# ESP32WROOM.net
KiCad netlist of a schematic drawn in Altium Designer
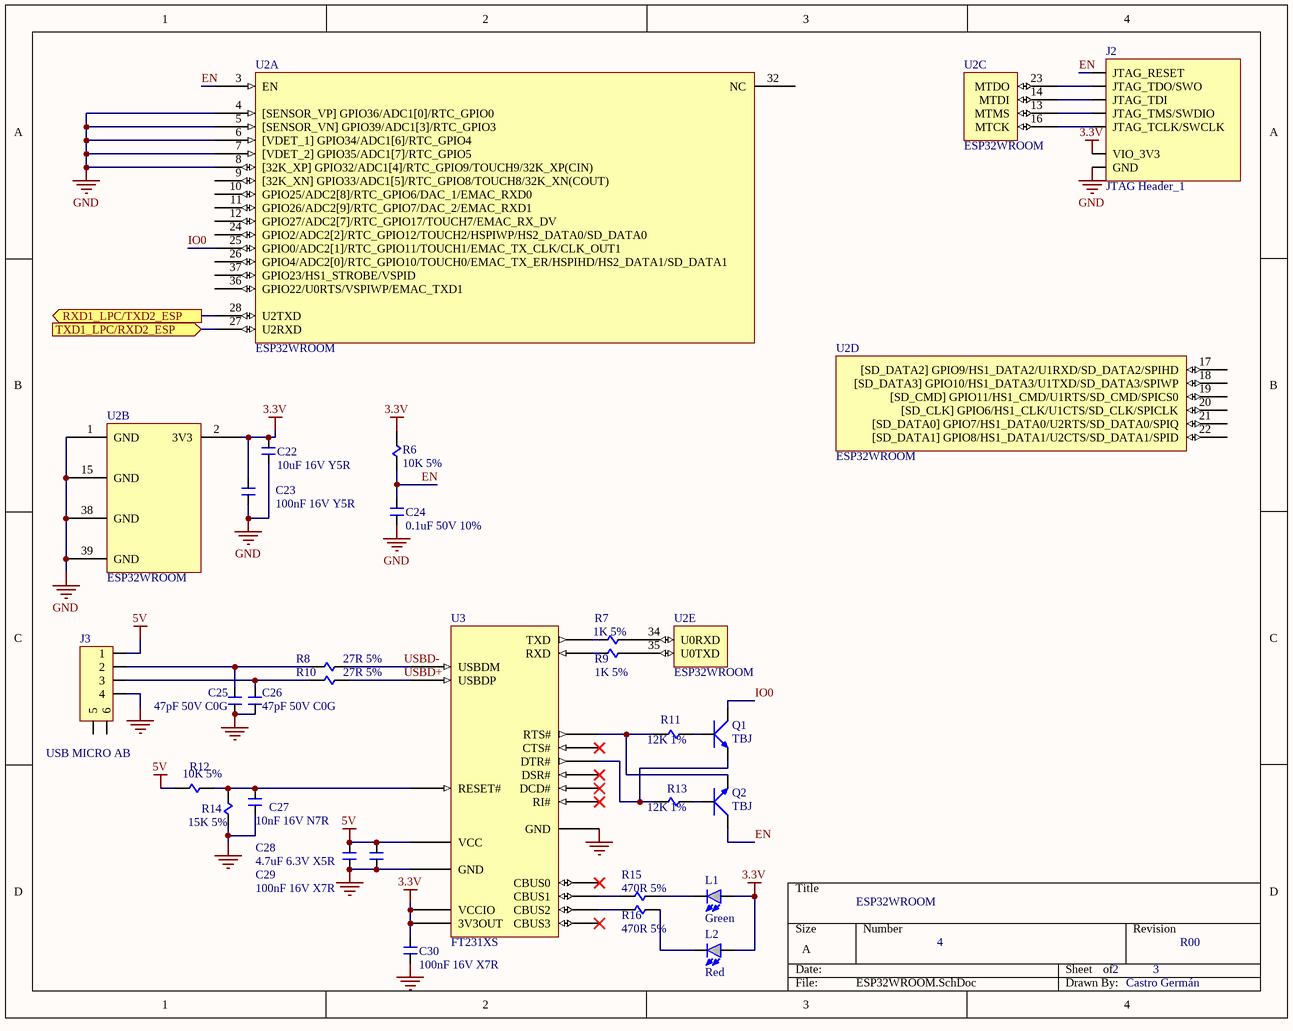
[diagram p0: ESP32WROOM.SchDoc]

(export (version "E")
  (design (tool "Eeschema 10.0.6"))
  (components
    (comp (ref "C22")
      (value "10uF 16V Y5R")
      (footprint "C_0805")
      (description "Capacitor")
      (libsource (lib "MyPro") (part "Capacitor"))
    )
    (comp (ref "C23")
      (value "100nF 16V Y5R")
      (footprint "C_0805")
      (description "Capacitor")
      (libsource (lib "MyPro") (part "Capacitor"))
    )
    (comp (ref "C24")
      (value "0.1uF 50V 10%")
      (footprint "C_0805")
      (description "Capacitor")
      (libsource (lib "MyPro") (part "Capacitor"))
    )
    (comp (ref "C25")
      (value "47pF 50V C0G")
      (footprint "C_0805")
      (description "Capacitor")
      (libsource (lib "BridgeUSB") (part "Capacitor"))
    )
    (comp (ref "C26")
      (value "47pF 50V C0G")
      (footprint "C_0805")
      (description "Capacitor")
      (libsource (lib "BridgeUSB") (part "Capacitor"))
    )
    (comp (ref "C27")
      (value "10nF 16V N7R")
      (footprint "C_0805")
      (description "Capacitor")
      (libsource (lib "BridgeUSB") (part "Capacitor"))
    )
    (comp (ref "C28")
      (value "4.7uF 6.3V X5R")
      (footprint "C_0805")
      (description "Capacitor")
      (libsource (lib "BridgeUSB") (part "Capacitor"))
    )
    (comp (ref "C29")
      (value "100nF 16V X7R")
      (footprint "C_0805")
      (description "Capacitor")
      (libsource (lib "BridgeUSB") (part "Capacitor"))
    )
    (comp (ref "C30")
      (value "100nF 16V X7R")
      (footprint "C_0805")
      (description "Capacitor")
      (libsource (lib "BridgeUSB") (part "Capacitor"))
    )
    (comp (ref "J2")
      (value "JTAG Header_1")
      (footprint "HDRM_2.54mm_1X8")
      (libsource (lib "MyPro") (part "JTAG Header_1"))
    )
    (comp (ref "J3")
      (value "USB MICRO AB")
      (footprint "USB_MICRO_F_AB")
      (libsource (lib "BridgeUSB") (part "Connectorx6"))
    )
    (comp (ref "L1")
      (value "Green")
      (footprint "Led_0805")
      (description "Green LED")
      (libsource (lib "MyPro") (part "Led_G"))
    )
    (comp (ref "L2")
      (value "Red")
      (footprint "Led_0805")
      (description "Red LED")
      (libsource (lib "MyPro") (part "Led_R"))
    )
    (comp (ref "Q1") (value "TBJ") (footprint "SOT-23") (libsource (lib "MyPro") (part "TBJ_NPN")))
    (comp (ref "Q2") (value "TBJ") (footprint "SOT-23") (libsource (lib "MyPro") (part "TBJ_NPN")))
    (comp (ref "R6")
      (value "10K 5%")
      (footprint "R_0805")
      (description "Resistor")
      (libsource (lib "MyPro") (part "Resistor"))
    )
    (comp (ref "R7")
      (value "1K 5%")
      (footprint "R_0805")
      (description "Resistor")
      (libsource (lib "BridgeUSB") (part "Resistor"))
    )
    (comp (ref "R8")
      (value "27R 5%")
      (footprint "R_0805")
      (description "Resistor")
      (libsource (lib "BridgeUSB") (part "Resistor"))
    )
    (comp (ref "R9")
      (value "1K 5%")
      (footprint "R_0805")
      (description "Resistor")
      (libsource (lib "BridgeUSB") (part "Resistor"))
    )
    (comp (ref "R10")
      (value "27R 5%")
      (footprint "R_0805")
      (description "Resistor")
      (libsource (lib "BridgeUSB") (part "Resistor"))
    )
    (comp (ref "R11")
      (value "12K 1%")
      (footprint "R_0805")
      (description "Resistor")
      (libsource (lib "MyPro") (part "Resistor"))
    )
    (comp (ref "R12")
      (value "10K 5%")
      (footprint "R_0805")
      (description "Resistor")
      (libsource (lib "BridgeUSB") (part "Resistor"))
    )
    (comp (ref "R13")
      (value "12K 1%")
      (footprint "R_0805")
      (description "Resistor")
      (libsource (lib "MyPro") (part "Resistor"))
    )
    (comp (ref "R14")
      (value "15K 5%")
      (footprint "R_0805")
      (description "Resistor")
      (libsource (lib "BridgeUSB") (part "Resistor"))
    )
    (comp (ref "R15")
      (value "470R 5%")
      (footprint "R_0805")
      (description "Resistor")
      (libsource (lib "BridgeUSB") (part "Resistor"))
    )
    (comp (ref "R16")
      (value "470R 5%")
      (footprint "R_0805")
      (description "Resistor")
      (libsource (lib "BridgeUSB") (part "Resistor"))
    )
    (comp (ref "U2")
      (value "ESP32WROOM")
      (footprint "ESP32_WROOM - duplicate")
      (libsource (lib "MyPro") (part "ESP32WROOM"))
    )
    (comp (ref "U3") (value "FT231XS") (footprint "SSOP_20") (libsource (lib "MyPro") (part "FT231XS")))
  )
  (nets
    (net (code "1") (name "/EN") (class "Default")
      (node (ref "C24") (pin "1") (pinfunction "A1_1") (pintype "passive"))
      (node (ref "J2") (pin "4") (pinfunction "JTAG_RESET_4") (pintype "passive"))
      (node (ref "Q2") (pin "3") (pinfunction "C_3") (pintype "passive"))
      (node (ref "R6") (pin "1") (pinfunction "P1_1") (pintype "passive"))
      (node (ref "U2") (pin "3") (pinfunction "EN_3") (pintype "input"))
    )
    (net (code "2") (name "/IO0") (class "Default")
      (node (ref "Q1") (pin "3") (pinfunction "C_3") (pintype "passive"))
      (node (ref "U2") (pin "25") (pinfunction "GPIO0/ADC2[1]/RTC_GPIO11/TOUCH1/EMAC_TX_CLK/CLK_OUT1_25") (pintype "bidirectional"))
    )
    (net (code "3") (name "/RXD1_LPC{slash}TXD2_ESP") (class "Default")
      (node (ref "U2") (pin "28") (pinfunction "U2TXD_28") (pintype "bidirectional"))
    )
    (net (code "4") (name "/TXD1_LPC{slash}RXD2_ESP") (class "Default")
      (node (ref "U2") (pin "27") (pinfunction "U2RXD_27") (pintype "bidirectional"))
    )
    (net (code "5") (name "/USBD+") (class "Default")
      (node (ref "R10") (pin "2") (pinfunction "P2_2") (pintype "passive"))
      (node (ref "U3") (pin "11") (pinfunction "USBDP_11") (pintype "input"))
    )
    (net (code "6") (name "/USBD-") (class "Default")
      (node (ref "R8") (pin "2") (pinfunction "P2_2") (pintype "passive"))
      (node (ref "U3") (pin "12") (pinfunction "USBDM_12") (pintype "input"))
    )
    (net (code "7") (name "3.3V") (class "Default")
      (node (ref "C22") (pin "1") (pinfunction "A1_1") (pintype "passive"))
      (node (ref "C23") (pin "1") (pinfunction "A1_1") (pintype "passive"))
      (node (ref "C30") (pin "1") (pinfunction "A1_1") (pintype "passive"))
      (node (ref "J2") (pin "1") (pinfunction "VIO_3V3_1") (pintype "passive"))
      (node (ref "L1") (pin "1") (pinfunction "A_1") (pintype "passive"))
      (node (ref "L2") (pin "1") (pinfunction "A_1") (pintype "passive"))
      (node (ref "R6") (pin "2") (pinfunction "P2_2") (pintype "passive"))
      (node (ref "U2") (pin "2") (pinfunction "3V3_2") (pintype "passive"))
      (node (ref "U3") (pin "13") (pinfunction "3V3OUT_13") (pintype "power_in"))
      (node (ref "U3") (pin "3") (pinfunction "VCCIO_3") (pintype "power_in"))
    )
    (net (code "8") (name "5V") (class "Default")
      (node (ref "C28") (pin "1") (pinfunction "A1_1") (pintype "passive"))
      (node (ref "C29") (pin "1") (pinfunction "A1_1") (pintype "passive"))
      (node (ref "J3") (pin "1") (pinfunction "1_1") (pintype "passive"))
      (node (ref "R12") (pin "1") (pinfunction "P1_1") (pintype "passive"))
      (node (ref "U3") (pin "15") (pinfunction "VCC_15") (pintype "power_in"))
    )
    (net (code "9") (name "GND") (class "Default")
      (node (ref "C22") (pin "2") (pinfunction "A2_2") (pintype "passive"))
      (node (ref "C23") (pin "2") (pinfunction "A2_2") (pintype "passive"))
      (node (ref "C24") (pin "2") (pinfunction "A2_2") (pintype "passive"))
      (node (ref "C25") (pin "2") (pinfunction "A2_2") (pintype "passive"))
      (node (ref "C26") (pin "2") (pinfunction "A2_2") (pintype "passive"))
      (node (ref "C27") (pin "2") (pinfunction "A2_2") (pintype "passive"))
      (node (ref "C28") (pin "2") (pinfunction "A2_2") (pintype "passive"))
      (node (ref "C29") (pin "2") (pinfunction "A2_2") (pintype "passive"))
      (node (ref "C30") (pin "2") (pinfunction "A2_2") (pintype "passive"))
      (node (ref "J2") (pin "3") (pinfunction "GND_3") (pintype "passive"))
      (node (ref "J3") (pin "4") (pinfunction "4_4") (pintype "passive"))
      (node (ref "R14") (pin "2") (pinfunction "P2_2") (pintype "passive"))
      (node (ref "U2") (pin "1") (pinfunction "GND_1") (pintype "passive"))
      (node (ref "U2") (pin "15") (pinfunction "GND_15") (pintype "passive"))
      (node (ref "U2") (pin "38") (pinfunction "GND_38") (pintype "passive"))
      (node (ref "U2") (pin "39") (pinfunction "GND_39") (pintype "passive"))
      (node (ref "U2") (pin "4") (pinfunction "[SENSOR_VP]_GPIO36/ADC1[0]/RTC_GPIO0_4") (pintype "input"))
      (node (ref "U2") (pin "5") (pinfunction "[SENSOR_VN]_GPIO39/ADC1[3]/RTC_GPIO3_5") (pintype "input"))
      (node (ref "U2") (pin "6") (pinfunction "[VDET_1]_GPIO34/ADC1[6]/RTC_GPIO4_6") (pintype "input"))
      (node (ref "U2") (pin "7") (pinfunction "[VDET_2]_GPIO35/ADC1[7]/RTC_GPIO5_7") (pintype "input"))
      (node (ref "U2") (pin "8") (pinfunction "[32K_XP]_GPIO32/ADC1[4]/RTC_GPIO9/TOUCH9/32K_XP(CIN)_8") (pintype "bidirectional"))
      (node (ref "U3") (pin "16") (pinfunction "GND_16") (pintype "power_in"))
      (node (ref "U3") (pin "6") (pinfunction "GND_6") (pintype "power_in"))
    )
    (net (code "10") (name "Net-(C25-A1)") (class "Default")
      (node (ref "C25") (pin "1") (pinfunction "A1_1") (pintype "passive"))
      (node (ref "J3") (pin "2") (pinfunction "2_2") (pintype "passive"))
      (node (ref "R8") (pin "1") (pinfunction "P1_1") (pintype "passive"))
    )
    (net (code "11") (name "Net-(C26-A1)") (class "Default")
      (node (ref "C26") (pin "1") (pinfunction "A1_1") (pintype "passive"))
      (node (ref "J3") (pin "3") (pinfunction "3_3") (pintype "passive"))
      (node (ref "R10") (pin "1") (pinfunction "P1_1") (pintype "passive"))
    )
    (net (code "12") (name "Net-(C27-A1)") (class "Default")
      (node (ref "C27") (pin "1") (pinfunction "A1_1") (pintype "passive"))
      (node (ref "R12") (pin "2") (pinfunction "P2_2") (pintype "passive"))
      (node (ref "R14") (pin "1") (pinfunction "P1_1") (pintype "passive"))
      (node (ref "U3") (pin "14") (pinfunction "RESET#_14") (pintype "input"))
    )
    (net (code "13") (name "Net-(J2-JTAG_TCLK{slash}SWCLK)") (class "Default")
      (node (ref "J2") (pin "7") (pinfunction "JTAG_TCLK/SWCLK_7") (pintype "passive"))
      (node (ref "U2") (pin "16") (pinfunction "MTCK_16") (pintype "bidirectional"))
    )
    (net (code "14") (name "Net-(J2-JTAG_TDI)") (class "Default")
      (node (ref "J2") (pin "6") (pinfunction "JTAG_TDI_6") (pintype "passive"))
      (node (ref "U2") (pin "14") (pinfunction "MTDI_14") (pintype "bidirectional"))
    )
    (net (code "15") (name "Net-(J2-JTAG_TDO{slash}SWO)") (class "Default")
      (node (ref "J2") (pin "8") (pinfunction "JTAG_TDO/SWO_8") (pintype "passive"))
      (node (ref "U2") (pin "23") (pinfunction "MTDO_23") (pintype "bidirectional"))
    )
    (net (code "16") (name "Net-(J2-JTAG_TMS{slash}SWDIO)") (class "Default")
      (node (ref "J2") (pin "5") (pinfunction "JTAG_TMS/SWDIO_5") (pintype "passive"))
      (node (ref "U2") (pin "13") (pinfunction "MTMS_13") (pintype "bidirectional"))
    )
    (net (code "17") (name "Net-(L1-K)") (class "Default")
      (node (ref "L1") (pin "2") (pinfunction "K_2") (pintype "passive"))
      (node (ref "R15") (pin "2") (pinfunction "P2_2") (pintype "passive"))
    )
    (net (code "18") (name "Net-(L2-K)") (class "Default")
      (node (ref "L2") (pin "2") (pinfunction "K_2") (pintype "passive"))
      (node (ref "R16") (pin "2") (pinfunction "P2_2") (pintype "passive"))
    )
    (net (code "19") (name "Net-(Q1-B)") (class "Default")
      (node (ref "Q1") (pin "1") (pinfunction "B_1") (pintype "passive"))
      (node (ref "R11") (pin "2") (pinfunction "P2_2") (pintype "passive"))
    )
    (net (code "20") (name "Net-(Q1-E)") (class "Default")
      (node (ref "Q1") (pin "2") (pinfunction "E_2") (pintype "passive"))
      (node (ref "R13") (pin "1") (pinfunction "P1_1") (pintype "passive"))
      (node (ref "U3") (pin "1") (pinfunction "DTR#_1") (pintype "output"))
    )
    (net (code "21") (name "Net-(Q2-B)") (class "Default")
      (node (ref "Q2") (pin "1") (pinfunction "B_1") (pintype "passive"))
      (node (ref "R13") (pin "2") (pinfunction "P2_2") (pintype "passive"))
    )
    (net (code "22") (name "Net-(Q2-E)") (class "Default")
      (node (ref "Q2") (pin "2") (pinfunction "E_2") (pintype "passive"))
      (node (ref "R11") (pin "1") (pinfunction "P1_1") (pintype "passive"))
      (node (ref "U3") (pin "2") (pinfunction "RTS#_2") (pintype "output"))
    )
    (net (code "23") (name "Net-(R7-P1)") (class "Default")
      (node (ref "R7") (pin "1") (pinfunction "P1_1") (pintype "passive"))
      (node (ref "U3") (pin "20") (pinfunction "TXD_20") (pintype "output"))
    )
    (net (code "24") (name "Net-(R7-P2)") (class "Default")
      (node (ref "R7") (pin "2") (pinfunction "P2_2") (pintype "passive"))
      (node (ref "U2") (pin "34") (pinfunction "U0RXD_34") (pintype "bidirectional"))
    )
    (net (code "25") (name "Net-(R9-P1)") (class "Default")
      (node (ref "R9") (pin "1") (pinfunction "P1_1") (pintype "passive"))
      (node (ref "U3") (pin "4") (pinfunction "RXD_4") (pintype "input"))
    )
    (net (code "26") (name "Net-(R9-P2)") (class "Default")
      (node (ref "R9") (pin "2") (pinfunction "P2_2") (pintype "passive"))
      (node (ref "U2") (pin "35") (pinfunction "U0TXD_35") (pintype "bidirectional"))
    )
    (net (code "27") (name "Net-(R15-P1)") (class "Default")
      (node (ref "R15") (pin "1") (pinfunction "P1_1") (pintype "passive"))
      (node (ref "U3") (pin "17") (pinfunction "CBUS1_17") (pintype "bidirectional"))
    )
    (net (code "28") (name "Net-(R16-P1)") (class "Default")
      (node (ref "R16") (pin "1") (pinfunction "P1_1") (pintype "passive"))
      (node (ref "U3") (pin "10") (pinfunction "CBUS2_10") (pintype "bidirectional"))
    )
    (net (code "29") (name "unconnected-(J3-Pad5)") (class "Default")
      (node (ref "J3") (pin "5") (pinfunction "5_5") (pintype "passive"))
    )
    (net (code "30") (name "unconnected-(J3-Pad6)") (class "Default")
      (node (ref "J3") (pin "6") (pinfunction "6_6") (pintype "passive"))
    )
    (net (code "31") (name "unconnected-(U2A-GPIO2{slash}ADC2[2]{slash}RTC_GPIO12{slash}TOUCH2{slash}HSPIWP{slash}HS2_DATA0{slash}SD_DATA0-Pad24)") (class "Default")
      (node (ref "U2") (pin "24") (pinfunction "GPIO2/ADC2[2]/RTC_GPIO12/TOUCH2/HSPIWP/HS2_DATA0/SD_DATA0_24") (pintype "bidirectional"))
    )
    (net (code "32") (name "unconnected-(U2A-GPIO4{slash}ADC2[0]{slash}RTC_GPIO10{slash}TOUCH0{slash}EMAC_TX_ER{slash}HSPIHD{slash}HS2_DATA1{slash}SD_DATA1-Pad26)") (class "Default")
      (node (ref "U2") (pin "26") (pinfunction "GPIO4/ADC2[0]/RTC_GPIO10/TOUCH0/EMAC_TX_ER/HSPIHD/HS2_DATA1/SD_DATA1_26") (pintype "bidirectional"))
    )
    (net (code "33") (name "unconnected-(U2A-GPIO22{slash}U0RTS{slash}VSPIWP{slash}EMAC_TXD1-Pad36)") (class "Default")
      (node (ref "U2") (pin "36") (pinfunction "GPIO22/U0RTS/VSPIWP/EMAC_TXD1_36") (pintype "bidirectional"))
    )
    (net (code "34") (name "unconnected-(U2A-GPIO23{slash}HS1_STROBE{slash}VSPID-Pad37)") (class "Default")
      (node (ref "U2") (pin "37") (pinfunction "GPIO23/HS1_STROBE/VSPID_37") (pintype "bidirectional"))
    )
    (net (code "35") (name "unconnected-(U2A-GPIO25{slash}ADC2[8]{slash}RTC_GPIO6{slash}DAC_1{slash}EMAC_RXD0-Pad10)") (class "Default")
      (node (ref "U2") (pin "10") (pinfunction "GPIO25/ADC2[8]/RTC_GPIO6/DAC_1/EMAC_RXD0_10") (pintype "bidirectional"))
    )
    (net (code "36") (name "unconnected-(U2A-GPIO26{slash}ADC2[9]{slash}RTC_GPIO7{slash}DAC_2{slash}EMAC_RXD1-Pad11)") (class "Default")
      (node (ref "U2") (pin "11") (pinfunction "GPIO26/ADC2[9]/RTC_GPIO7/DAC_2/EMAC_RXD1_11") (pintype "bidirectional"))
    )
    (net (code "37") (name "unconnected-(U2A-GPIO27{slash}ADC2[7]{slash}RTC_GPIO17{slash}TOUCH7{slash}EMAC_RX_DV-Pad12)") (class "Default")
      (node (ref "U2") (pin "12") (pinfunction "GPIO27/ADC2[7]/RTC_GPIO17/TOUCH7/EMAC_RX_DV_12") (pintype "bidirectional"))
    )
    (net (code "38") (name "unconnected-(U2A-NC-Pad32)") (class "Default")
      (node (ref "U2") (pin "32") (pinfunction "NC_32") (pintype "passive"))
    )
    (net (code "39") (name "unconnected-(U2A-[32K_XN]_GPIO33{slash}ADC1[5]{slash}RTC_GPIO8{slash}TOUCH8{slash}32K_XN(COUT)-Pad9)") (class "Default")
      (node (ref "U2") (pin "9") (pinfunction "[32K_XN]_GPIO33/ADC1[5]/RTC_GPIO8/TOUCH8/32K_XN(COUT)_9") (pintype "bidirectional"))
    )
    (net (code "40") (name "unconnected-(U2D-[SD_CLK]_GPIO6{slash}HS1_CLK{slash}U1CTS{slash}SD_CLK{slash}SPICLK-Pad20)") (class "Default")
      (node (ref "U2") (pin "20") (pinfunction "[SD_CLK]_GPIO6/HS1_CLK/U1CTS/SD_CLK/SPICLK_20") (pintype "bidirectional"))
    )
    (net (code "41") (name "unconnected-(U2D-[SD_CMD]_GPIO11{slash}HS1_CMD{slash}U1RTS{slash}SD_CMD{slash}SPICS0-Pad19)") (class "Default")
      (node (ref "U2") (pin "19") (pinfunction "[SD_CMD]_GPIO11/HS1_CMD/U1RTS/SD_CMD/SPICS0_19") (pintype "bidirectional"))
    )
    (net (code "42") (name "unconnected-(U2D-[SD_DATA0]_GPIO7{slash}HS1_DATA0{slash}U2RTS{slash}SD_DATA0{slash}SPIQ-Pad21)") (class "Default")
      (node (ref "U2") (pin "21") (pinfunction "[SD_DATA0]_GPIO7/HS1_DATA0/U2RTS/SD_DATA0/SPIQ_21") (pintype "bidirectional"))
    )
    (net (code "43") (name "unconnected-(U2D-[SD_DATA1]_GPIO8{slash}HS1_DATA1{slash}U2CTS{slash}SD_DATA1{slash}SPID-Pad22)") (class "Default")
      (node (ref "U2") (pin "22") (pinfunction "[SD_DATA1]_GPIO8/HS1_DATA1/U2CTS/SD_DATA1/SPID_22") (pintype "bidirectional"))
    )
    (net (code "44") (name "unconnected-(U2D-[SD_DATA2]_GPIO9{slash}HS1_DATA2{slash}U1RXD{slash}SD_DATA2{slash}SPIHD-Pad17)") (class "Default")
      (node (ref "U2") (pin "17") (pinfunction "[SD_DATA2]_GPIO9/HS1_DATA2/U1RXD/SD_DATA2/SPIHD_17") (pintype "bidirectional"))
    )
    (net (code "45") (name "unconnected-(U2D-[SD_DATA3]_GPIO10{slash}HS1_DATA3{slash}U1TXD{slash}SD_DATA3{slash}SPIWP-Pad18)") (class "Default")
      (node (ref "U2") (pin "18") (pinfunction "[SD_DATA3]_GPIO10/HS1_DATA3/U1TXD/SD_DATA3/SPIWP_18") (pintype "bidirectional"))
    )
    (net (code "46") (name "unconnected-(U3-CBUS0-Pad18)") (class "Default")
      (node (ref "U3") (pin "18") (pinfunction "CBUS0_18") (pintype "bidirectional+no_connect"))
    )
    (net (code "47") (name "unconnected-(U3-CBUS3-Pad19)") (class "Default")
      (node (ref "U3") (pin "19") (pinfunction "CBUS3_19") (pintype "bidirectional+no_connect"))
    )
    (net (code "48") (name "unconnected-(U3-CTS#-Pad9)") (class "Default")
      (node (ref "U3") (pin "9") (pinfunction "CTS#_9") (pintype "input+no_connect"))
    )
    (net (code "49") (name "unconnected-(U3-DCD#-Pad8)") (class "Default")
      (node (ref "U3") (pin "8") (pinfunction "DCD#_8") (pintype "input+no_connect"))
    )
    (net (code "50") (name "unconnected-(U3-DSR#-Pad7)") (class "Default")
      (node (ref "U3") (pin "7") (pinfunction "DSR#_7") (pintype "input+no_connect"))
    )
    (net (code "51") (name "unconnected-(U3-RI#-Pad5)") (class "Default")
      (node (ref "U3") (pin "5") (pinfunction "RI#_5") (pintype "input+no_connect"))
    )
  )
)
